# JLPCB_DATA_LOGGER.net
KiCad netlist of a schematic drawn in EasyEDA
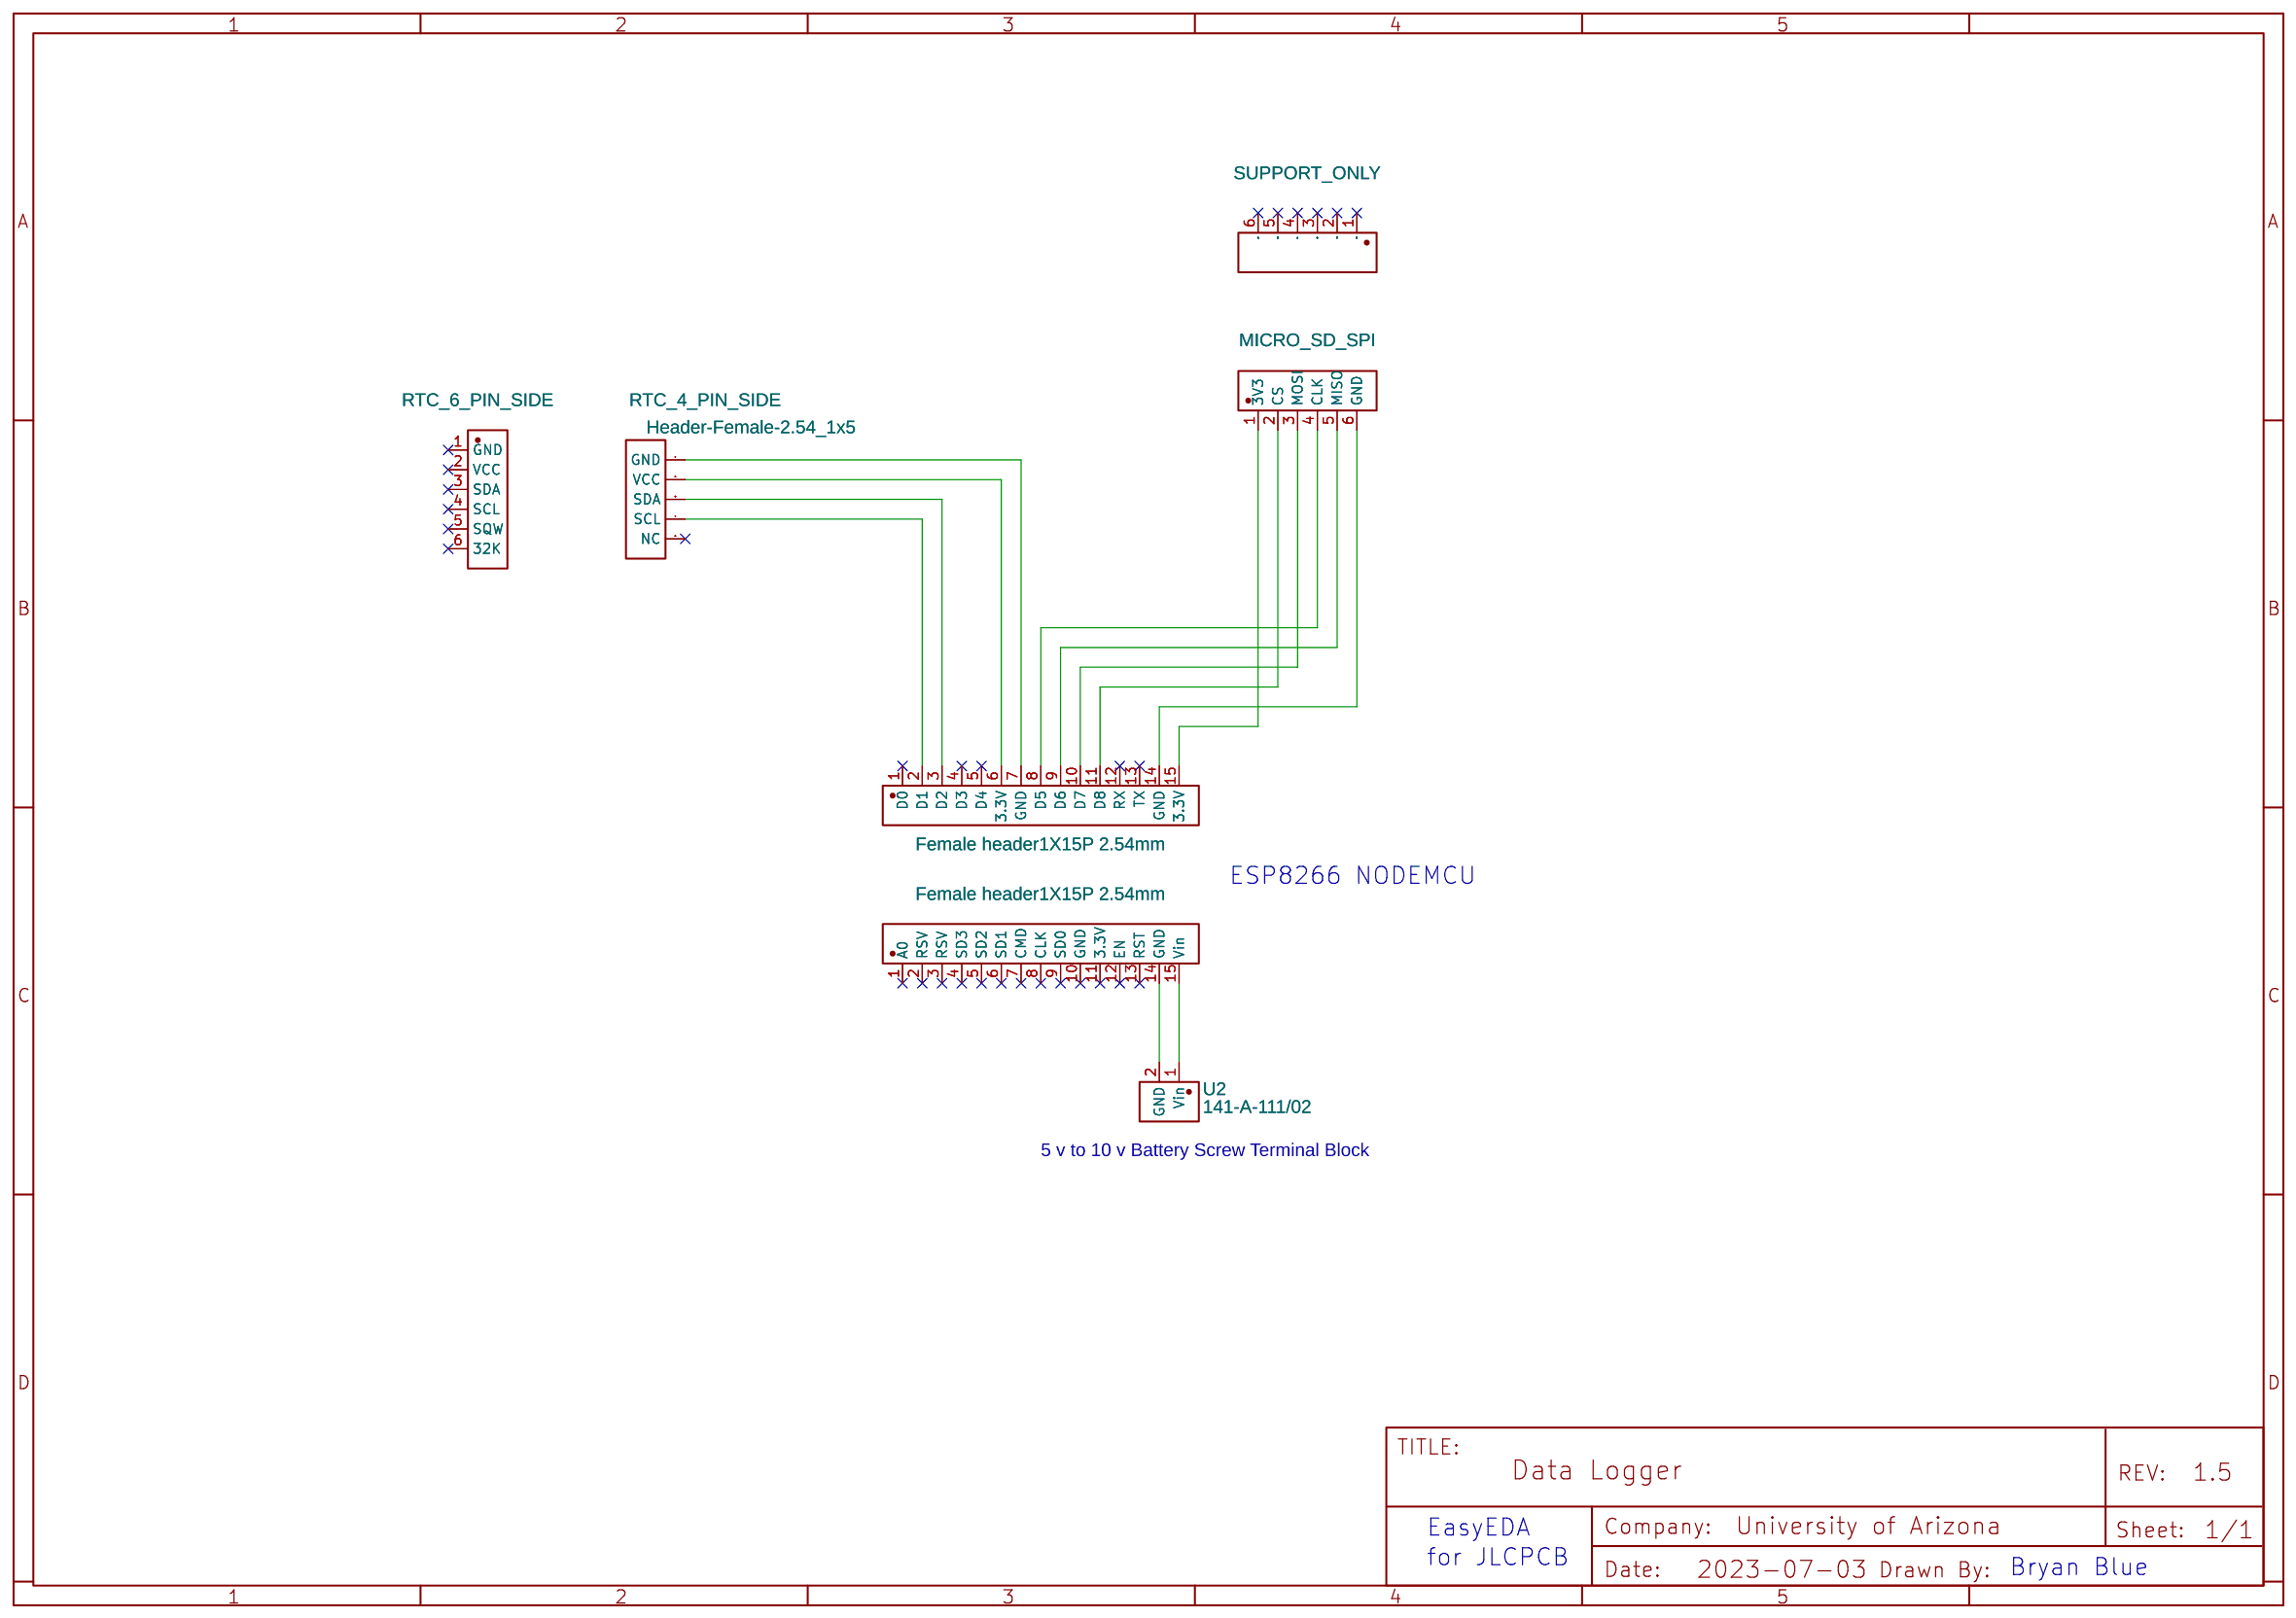
[diagram p0: schematic sheet]

(export (version "E")
  (design (tool "Eeschema 10.0.6"))
  (components
    (comp (ref "MICRO_SD_SPI")
      (value "Header-Female-2.54_1x6")
      (fields (field (name "BOM_Manufacturer Part") "2.54-1*6P母") (field (name "BOM_Supplier Part") "C40877"))
      (libsource (lib "") (part "Header-Female-2.54_1x6"))
    )
    (comp (ref "P1")
      (value "Female header1X15P 2.54mm")
      (fields (field (name "BOM_Supplier Part") "C54104"))
      (libsource (lib "") (part "Female header1X15P 2.54mm_1"))
    )
    (comp (ref "P2")
      (value "Female header1X15P 2.54mm")
      (fields (field (name "BOM_Supplier Part") "C54104"))
      (libsource (lib "") (part "Female header1X15P 2.54mm"))
    )
    (comp (ref "RTC_4_PIN_SIDE")
      (value "Header-Female-2.54_1x5")
      (fields (field (name "BOM_Manufacturer Part") "2.54-1*5P母") (field (name "BOM_Supplier Part") "C50950"))
      (libsource (lib "") (part "Header-Female-2.54_1x5"))
    )
    (comp (ref "RTC_6_PIN_SIDE")
      (value "Header-Female-2.54_1x6")
      (fields (field (name "BOM_Manufacturer Part") "2.54-1*6P母") (field (name "BOM_Supplier Part") "C40877"))
      (libsource (lib "") (part "Header-Female-2.54_1x6_2"))
    )
    (comp (ref "SUPPORT_ONLY")
      (value "Header-Female-2.54_1x6")
      (fields (field (name "BOM_Manufacturer Part") "2.54-1*6P母") (field (name "BOM_Supplier Part") "C40877"))
      (libsource (lib "") (part "Header-Female-2.54_1x6_1"))
    )
    (comp (ref "U2")
      (value "141-A-111/02")
      (fields (field (name "BOM_Supplier Part") "C3011914"))
      (libsource (lib "") (part "141-A-111/02"))
    )
  )
  (nets
    (net (code "1") (name "Net-(MICRO_SD_SPI-3V3)") (class "Default")
      (node (ref "MICRO_SD_SPI") (pin "1") (pinfunction "3V3_1") (pintype "unspecified"))
      (node (ref "P2") (pin "15") (pinfunction "3.3V_15") (pintype "unspecified"))
    )
    (net (code "2") (name "Net-(MICRO_SD_SPI-CLK)") (class "Default")
      (node (ref "MICRO_SD_SPI") (pin "4") (pinfunction "CLK_4") (pintype "unspecified"))
      (node (ref "P2") (pin "8") (pinfunction "D5_8") (pintype "unspecified"))
    )
    (net (code "3") (name "Net-(MICRO_SD_SPI-CS)") (class "Default")
      (node (ref "MICRO_SD_SPI") (pin "2") (pinfunction "CS_2") (pintype "unspecified"))
      (node (ref "P2") (pin "11") (pinfunction "D8_11") (pintype "unspecified"))
    )
    (net (code "4") (name "Net-(MICRO_SD_SPI-GND)") (class "Default")
      (node (ref "MICRO_SD_SPI") (pin "6") (pinfunction "GND_6") (pintype "unspecified"))
      (node (ref "P2") (pin "14") (pinfunction "GND_14") (pintype "unspecified"))
    )
    (net (code "5") (name "Net-(MICRO_SD_SPI-MISO)") (class "Default")
      (node (ref "MICRO_SD_SPI") (pin "5") (pinfunction "MISO_5") (pintype "unspecified"))
      (node (ref "P2") (pin "9") (pinfunction "D6_9") (pintype "unspecified"))
    )
    (net (code "6") (name "Net-(MICRO_SD_SPI-MOSI)") (class "Default")
      (node (ref "MICRO_SD_SPI") (pin "3") (pinfunction "MOSI_3") (pintype "unspecified"))
      (node (ref "P2") (pin "10") (pinfunction "D7_10") (pintype "unspecified"))
    )
    (net (code "7") (name "Net-(P1-Vin)") (class "Default")
      (node (ref "P1") (pin "15") (pinfunction "Vin_15") (pintype "passive"))
      (node (ref "U2") (pin "1") (pinfunction "Vin_1") (pintype "unspecified"))
    )
    (net (code "8") (name "Net-(P2-D1)") (class "Default")
      (node (ref "P2") (pin "2") (pinfunction "D1_2") (pintype "unspecified"))
      (node (ref "RTC_4_PIN_SIDE") (pin "4") (pinfunction "SCL_4") (pintype "input"))
    )
    (net (code "9") (name "Net-(P2-D2)") (class "Default")
      (node (ref "P2") (pin "3") (pinfunction "D2_3") (pintype "unspecified"))
      (node (ref "RTC_4_PIN_SIDE") (pin "3") (pinfunction "SDA_3") (pintype "input"))
    )
    (net (code "10") (name "Net-(RTC_4_PIN_SIDE-GND)") (class "Default")
      (node (ref "P2") (pin "7") (pinfunction "GND_7") (pintype "unspecified"))
      (node (ref "RTC_4_PIN_SIDE") (pin "1") (pinfunction "GND_1") (pintype "input"))
    )
    (net (code "11") (name "Net-(RTC_4_PIN_SIDE-VCC)") (class "Default")
      (node (ref "P2") (pin "6") (pinfunction "3.3V_6") (pintype "unspecified"))
      (node (ref "RTC_4_PIN_SIDE") (pin "2") (pinfunction "VCC_2") (pintype "input"))
    )
    (net (code "12") (name "Net-(U2-GND)") (class "Default")
      (node (ref "P1") (pin "14") (pinfunction "GND_14") (pintype "passive"))
      (node (ref "U2") (pin "2") (pinfunction "GND_2") (pintype "unspecified"))
    )
    (net (code "13") (name "unconnected-(P1-3.3V-Pad11)") (class "Default")
      (node (ref "P1") (pin "11") (pinfunction "3.3V_11") (pintype "passive+no_connect"))
    )
    (net (code "14") (name "unconnected-(P1-A0-Pad1)") (class "Default")
      (node (ref "P1") (pin "1") (pinfunction "A0_1") (pintype "unspecified+no_connect"))
    )
    (net (code "15") (name "unconnected-(P1-CLK-Pad8)") (class "Default")
      (node (ref "P1") (pin "8") (pinfunction "CLK_8") (pintype "unspecified+no_connect"))
    )
    (net (code "16") (name "unconnected-(P1-CMD-Pad7)") (class "Default")
      (node (ref "P1") (pin "7") (pinfunction "CMD_7") (pintype "unspecified+no_connect"))
    )
    (net (code "17") (name "unconnected-(P1-EN-Pad12)") (class "Default")
      (node (ref "P1") (pin "12") (pinfunction "EN_12") (pintype "unspecified+no_connect"))
    )
    (net (code "18") (name "unconnected-(P1-GND-Pad10)") (class "Default")
      (node (ref "P1") (pin "10") (pinfunction "GND_10") (pintype "passive+no_connect"))
    )
    (net (code "19") (name "unconnected-(P1-RST-Pad13)") (class "Default")
      (node (ref "P1") (pin "13") (pinfunction "RST_13") (pintype "unspecified+no_connect"))
    )
    (net (code "20") (name "unconnected-(P1-RSV-Pad2)") (class "Default")
      (node (ref "P1") (pin "2") (pinfunction "RSV_2") (pintype "unspecified+no_connect"))
    )
    (net (code "21") (name "unconnected-(P1-RSV-Pad3)") (class "Default")
      (node (ref "P1") (pin "3") (pinfunction "RSV_3") (pintype "unspecified+no_connect"))
    )
    (net (code "22") (name "unconnected-(P1-SD0-Pad9)") (class "Default")
      (node (ref "P1") (pin "9") (pinfunction "SD0_9") (pintype "unspecified+no_connect"))
    )
    (net (code "23") (name "unconnected-(P1-SD1-Pad6)") (class "Default")
      (node (ref "P1") (pin "6") (pinfunction "SD1_6") (pintype "unspecified+no_connect"))
    )
    (net (code "24") (name "unconnected-(P1-SD2-Pad5)") (class "Default")
      (node (ref "P1") (pin "5") (pinfunction "SD2_5") (pintype "unspecified+no_connect"))
    )
    (net (code "25") (name "unconnected-(P1-SD3-Pad4)") (class "Default")
      (node (ref "P1") (pin "4") (pinfunction "SD3_4") (pintype "unspecified+no_connect"))
    )
    (net (code "26") (name "unconnected-(P2-D0-Pad1)") (class "Default")
      (node (ref "P2") (pin "1") (pinfunction "D0_1") (pintype "unspecified+no_connect"))
    )
    (net (code "27") (name "unconnected-(P2-D3-Pad4)") (class "Default")
      (node (ref "P2") (pin "4") (pinfunction "D3_4") (pintype "unspecified+no_connect"))
    )
    (net (code "28") (name "unconnected-(P2-D4-Pad5)") (class "Default")
      (node (ref "P2") (pin "5") (pinfunction "D4_5") (pintype "unspecified+no_connect"))
    )
    (net (code "29") (name "unconnected-(P2-RX-Pad12)") (class "Default")
      (node (ref "P2") (pin "12") (pinfunction "RX_12") (pintype "unspecified+no_connect"))
    )
    (net (code "30") (name "unconnected-(P2-TX-Pad13)") (class "Default")
      (node (ref "P2") (pin "13") (pinfunction "TX_13") (pintype "unspecified+no_connect"))
    )
    (net (code "31") (name "unconnected-(RTC_4_PIN_SIDE-NC-Pad5)") (class "Default")
      (node (ref "RTC_4_PIN_SIDE") (pin "5") (pinfunction "NC_5") (pintype "input+no_connect"))
    )
    (net (code "32") (name "unconnected-(RTC_6_PIN_SIDE-32K-Pad6)") (class "Default")
      (node (ref "RTC_6_PIN_SIDE") (pin "6") (pinfunction "32K_6") (pintype "unspecified+no_connect"))
    )
    (net (code "33") (name "unconnected-(RTC_6_PIN_SIDE-GND-Pad1)") (class "Default")
      (node (ref "RTC_6_PIN_SIDE") (pin "1") (pinfunction "GND_1") (pintype "unspecified+no_connect"))
    )
    (net (code "34") (name "unconnected-(RTC_6_PIN_SIDE-SCL-Pad4)") (class "Default")
      (node (ref "RTC_6_PIN_SIDE") (pin "4") (pinfunction "SCL_4") (pintype "unspecified+no_connect"))
    )
    (net (code "35") (name "unconnected-(RTC_6_PIN_SIDE-SDA-Pad3)") (class "Default")
      (node (ref "RTC_6_PIN_SIDE") (pin "3") (pinfunction "SDA_3") (pintype "unspecified+no_connect"))
    )
    (net (code "36") (name "unconnected-(RTC_6_PIN_SIDE-SQW-Pad5)") (class "Default")
      (node (ref "RTC_6_PIN_SIDE") (pin "5") (pinfunction "SQW_5") (pintype "unspecified+no_connect"))
    )
    (net (code "37") (name "unconnected-(RTC_6_PIN_SIDE-VCC-Pad2)") (class "Default")
      (node (ref "RTC_6_PIN_SIDE") (pin "2") (pinfunction "VCC_2") (pintype "unspecified+no_connect"))
    )
    (net (code "38") (name "unconnected-(SUPPORT_ONLY-3V3-Pad1)") (class "Default")
      (node (ref "SUPPORT_ONLY") (pin "1") (pinfunction "3V3_1") (pintype "unspecified+no_connect"))
    )
    (net (code "39") (name "unconnected-(SUPPORT_ONLY-CLK-Pad4)") (class "Default")
      (node (ref "SUPPORT_ONLY") (pin "4") (pinfunction "CLK_4") (pintype "unspecified+no_connect"))
    )
    (net (code "40") (name "unconnected-(SUPPORT_ONLY-CS-Pad2)") (class "Default")
      (node (ref "SUPPORT_ONLY") (pin "2") (pinfunction "CS_2") (pintype "unspecified+no_connect"))
    )
    (net (code "41") (name "unconnected-(SUPPORT_ONLY-GND-Pad6)") (class "Default")
      (node (ref "SUPPORT_ONLY") (pin "6") (pinfunction "GND_6") (pintype "unspecified+no_connect"))
    )
    (net (code "42") (name "unconnected-(SUPPORT_ONLY-MISO-Pad5)") (class "Default")
      (node (ref "SUPPORT_ONLY") (pin "5") (pinfunction "MISO_5") (pintype "unspecified+no_connect"))
    )
    (net (code "43") (name "unconnected-(SUPPORT_ONLY-MOSI-Pad3)") (class "Default")
      (node (ref "SUPPORT_ONLY") (pin "3") (pinfunction "MOSI_3") (pintype "unspecified+no_connect"))
    )
  )
)
